# Versa64Cart_v1_4.net
KiCad netlist of a schematic drawn in EAGLE
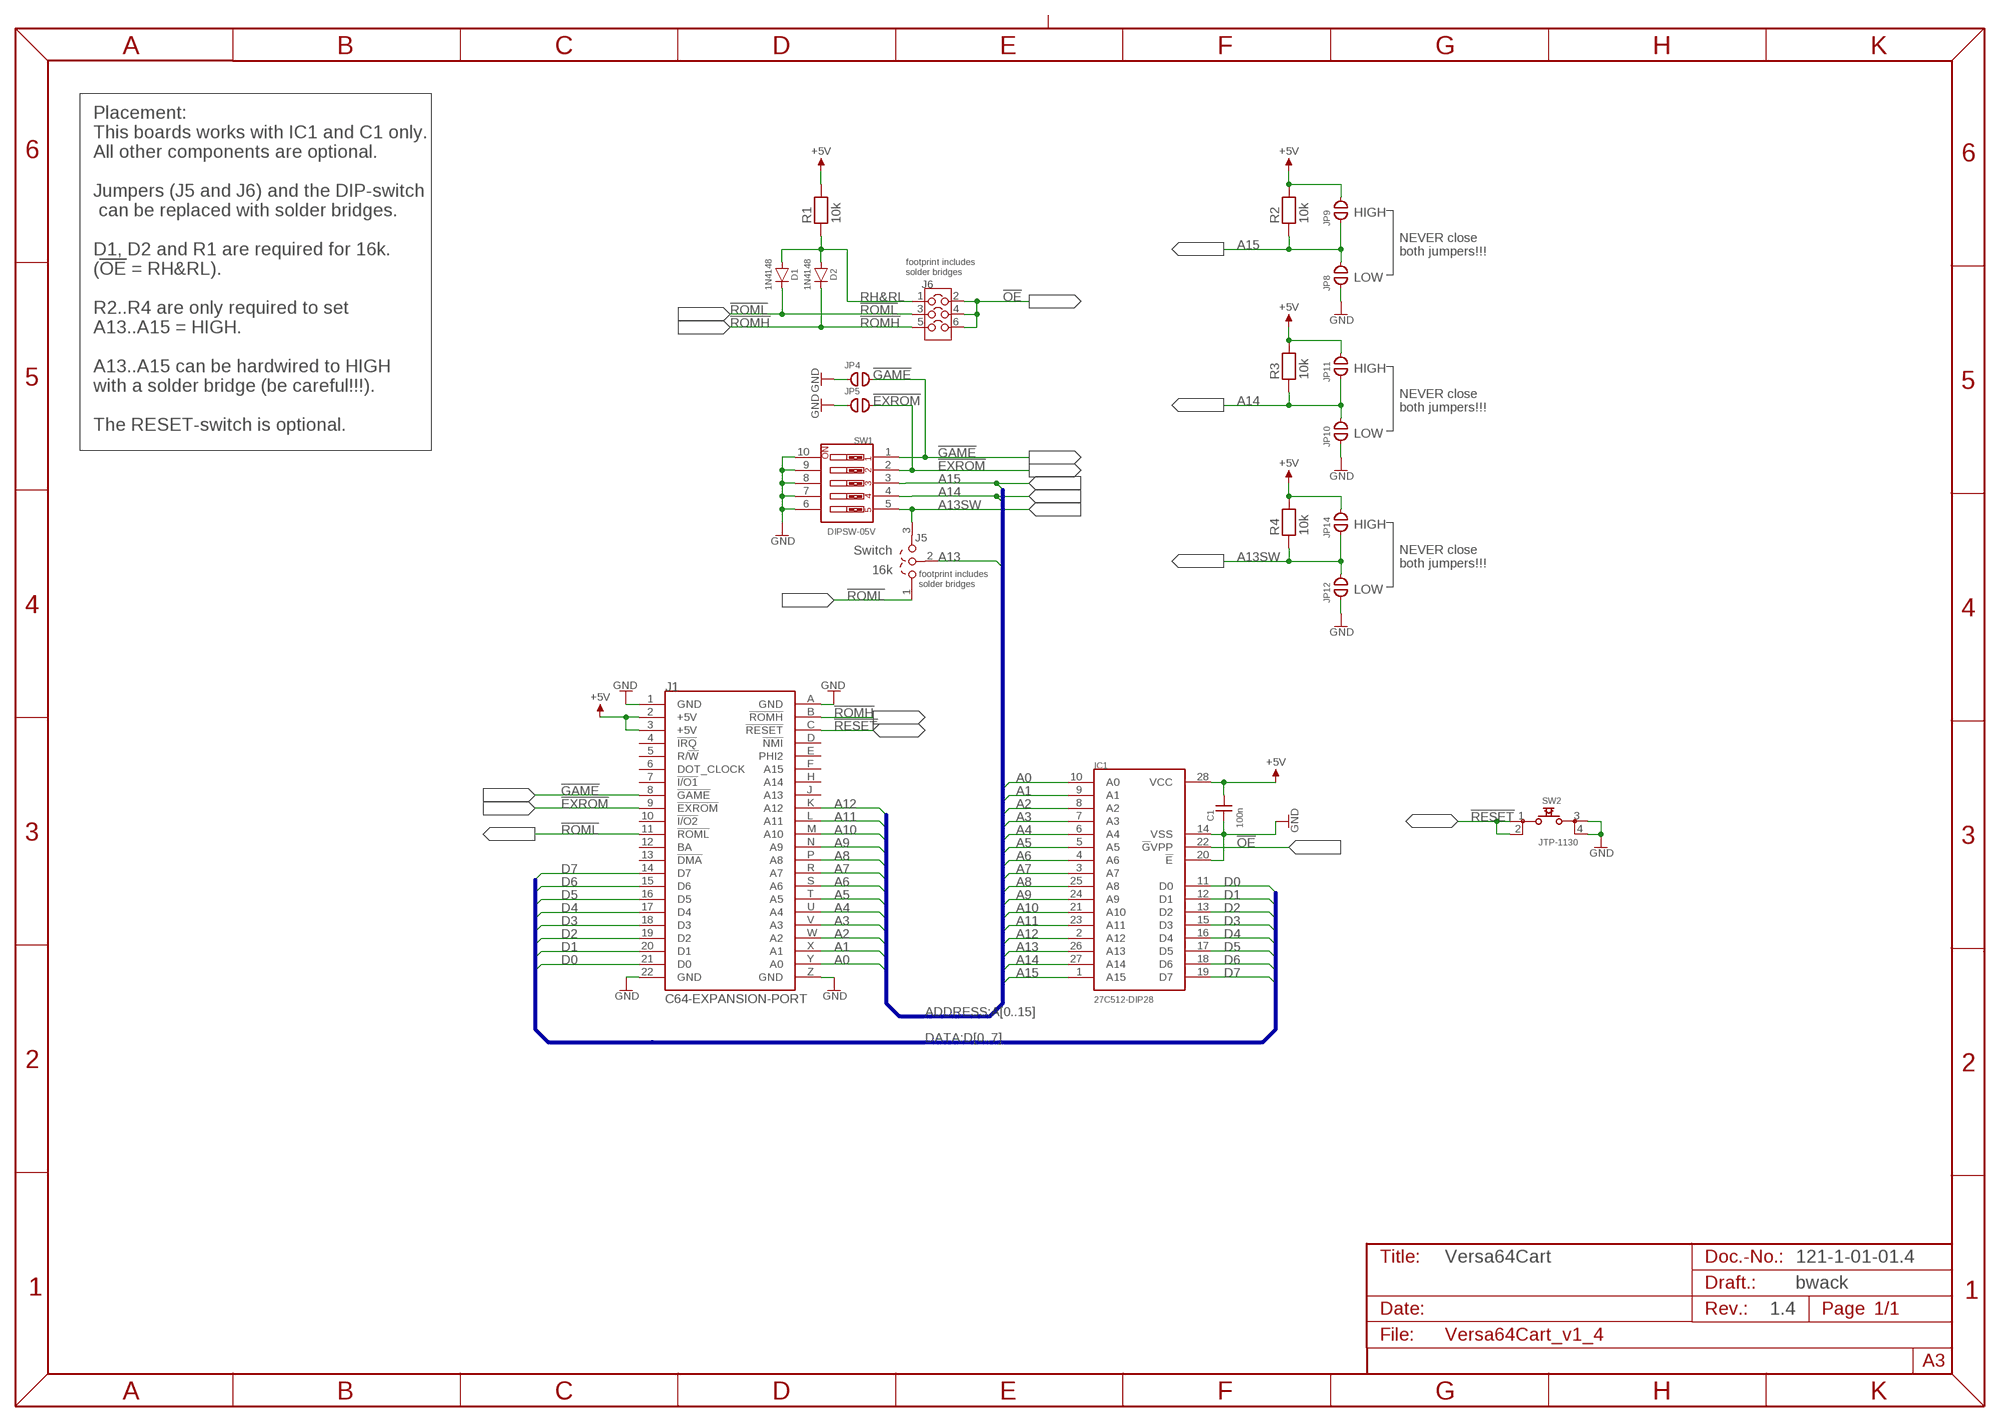
[diagram p0: schematic, sheet 1]

(export (version "E")
  (design (tool "Eeschema 10.0.6"))
  (components
    (comp (ref "C1")
      (value "100n")
      (footprint "eagle-import:C-2,5")
      (libsource (lib "eagle-import") (part "CAP01"))
    )
    (comp (ref "D1")
      (value "1N4148")
      (footprint "eagle-import:DO-35")
      (libsource (lib "eagle-import") (part "1N4148"))
    )
    (comp (ref "D2")
      (value "1N4148")
      (footprint "eagle-import:DO-35")
      (libsource (lib "eagle-import") (part "1N4148"))
    )
    (comp (ref "IC1")
      (value "27C512-DIP28")
      (footprint "eagle-import:DIL28-6")
      (libsource (lib "eagle-import") (part "M27C512-DIP28"))
    )
    (comp (ref "J1")
      (value "C64-EXPANSION-PORT")
      (footprint "eagle-import:EXPANSIO_SQ")
      (libsource (lib "eagle-import") (part "C64-EXPANSIONPNARROW"))
    )
    (comp (ref "J5")
      (value "COMBI-3P")
      (footprint "eagle-import:COMBI-3P")
      (libsource (lib "eagle-import") (part "COMBI-3P"))
    )
    (comp (ref "J6")
      (value "COMBI-3X2P")
      (footprint "eagle-import:COMBI-3X2")
      (fields (field (name "SPICEPREFIX") "X"))
      (libsource (lib "eagle-import") (part "COMBI-3X2P"))
    )
    (comp (ref "JP4")
      (value "OPEN")
      (footprint "eagle-import:CP_OP")
      (libsource (lib "eagle-import") (part "OPEN"))
    )
    (comp (ref "JP5")
      (value "OPEN")
      (footprint "eagle-import:CP_OP")
      (libsource (lib "eagle-import") (part "OPEN"))
    )
    (comp (ref "JP8")
      (value "OPEN")
      (footprint "eagle-import:CP_OP")
      (libsource (lib "eagle-import") (part "OPEN"))
    )
    (comp (ref "JP9")
      (value "OPEN")
      (footprint "eagle-import:CP_OP")
      (libsource (lib "eagle-import") (part "OPEN"))
    )
    (comp (ref "JP10")
      (value "OPEN")
      (footprint "eagle-import:CP_OP")
      (libsource (lib "eagle-import") (part "OPEN"))
    )
    (comp (ref "JP11")
      (value "OPEN")
      (footprint "eagle-import:CP_OP")
      (libsource (lib "eagle-import") (part "OPEN"))
    )
    (comp (ref "JP12")
      (value "OPEN")
      (footprint "eagle-import:CP_OP")
      (libsource (lib "eagle-import") (part "OPEN"))
    )
    (comp (ref "JP14")
      (value "OPEN")
      (footprint "eagle-import:CP_OP")
      (libsource (lib "eagle-import") (part "OPEN"))
    )
    (comp (ref "R1")
      (value "10k")
      (footprint "eagle-import:R-10")
      (libsource (lib "eagle-import") (part "RES04"))
    )
    (comp (ref "R2")
      (value "10k")
      (footprint "eagle-import:R-10")
      (libsource (lib "eagle-import") (part "RES04"))
    )
    (comp (ref "R3")
      (value "10k")
      (footprint "eagle-import:R-10")
      (libsource (lib "eagle-import") (part "RES04"))
    )
    (comp (ref "R4")
      (value "10k")
      (footprint "eagle-import:R-10")
      (libsource (lib "eagle-import") (part "RES04"))
    )
    (comp (ref "SW1")
      (value "DIPSW-05V")
      (footprint "eagle-import:DIPSW-05V")
      (libsource (lib "eagle-import") (part "DIPSW-05V"))
    )
    (comp (ref "SW2")
      (value "JTP-1130")
      (footprint "eagle-import:JTP-1130")
      (libsource (lib "eagle-import") (part "JTP-1130"))
    )
  )
  (nets
    (net (code "25") (name "+5V") (class "Default")
      (node (ref "C1") (pin "2") (pinfunction "2_2") (pintype "passive"))
      (node (ref "IC1") (pin "28") (pinfunction "VCC_28") (pintype "power_in"))
      (node (ref "J1") (pin "2") (pinfunction "+5V_2") (pintype "power_in"))
      (node (ref "J1") (pin "3") (pinfunction "+5V_3") (pintype "power_in"))
      (node (ref "JP11") (pin "2") (pinfunction "2_2") (pintype "passive"))
      (node (ref "JP14") (pin "2") (pinfunction "2_2") (pintype "passive"))
      (node (ref "JP9") (pin "2") (pinfunction "2_2") (pintype "passive"))
      (node (ref "R1") (pin "2") (pinfunction "2_2") (pintype "passive"))
      (node (ref "R2") (pin "2") (pinfunction "2_2") (pintype "passive"))
      (node (ref "R3") (pin "2") (pinfunction "2_2") (pintype "passive"))
      (node (ref "R4") (pin "2") (pinfunction "2_2") (pintype "passive"))
    )
    (net (code "26") (name "/A0") (class "Default")
      (node (ref "IC1") (pin "10") (pinfunction "A0_10") (pintype "input"))
      (node (ref "J1") (pin "Y") (pinfunction "A0_Y") (pintype "bidirectional"))
    )
    (net (code "27") (name "/A1") (class "Default")
      (node (ref "IC1") (pin "9") (pinfunction "A1_9") (pintype "input"))
      (node (ref "J1") (pin "X") (pinfunction "A1_X") (pintype "bidirectional"))
    )
    (net (code "28") (name "/A2") (class "Default")
      (node (ref "IC1") (pin "8") (pinfunction "A2_8") (pintype "input"))
      (node (ref "J1") (pin "W") (pinfunction "A2_W") (pintype "bidirectional"))
    )
    (net (code "29") (name "/A3") (class "Default")
      (node (ref "IC1") (pin "7") (pinfunction "A3_7") (pintype "input"))
      (node (ref "J1") (pin "V") (pinfunction "A3_V") (pintype "bidirectional"))
    )
    (net (code "30") (name "/A4") (class "Default")
      (node (ref "IC1") (pin "6") (pinfunction "A4_6") (pintype "input"))
      (node (ref "J1") (pin "U") (pinfunction "A4_U") (pintype "bidirectional"))
    )
    (net (code "31") (name "/A5") (class "Default")
      (node (ref "IC1") (pin "5") (pinfunction "A5_5") (pintype "input"))
      (node (ref "J1") (pin "T") (pinfunction "A5_T") (pintype "bidirectional"))
    )
    (net (code "32") (name "/A6") (class "Default")
      (node (ref "IC1") (pin "4") (pinfunction "A6_4") (pintype "input"))
      (node (ref "J1") (pin "S") (pinfunction "A6_S") (pintype "bidirectional"))
    )
    (net (code "33") (name "/A7") (class "Default")
      (node (ref "IC1") (pin "3") (pinfunction "A7_3") (pintype "input"))
      (node (ref "J1") (pin "R") (pinfunction "A7_R") (pintype "bidirectional"))
    )
    (net (code "34") (name "/A8") (class "Default")
      (node (ref "IC1") (pin "25") (pinfunction "A8_25") (pintype "input"))
      (node (ref "J1") (pin "P") (pinfunction "A8_P") (pintype "bidirectional"))
    )
    (net (code "35") (name "/A9") (class "Default")
      (node (ref "IC1") (pin "24") (pinfunction "A9_24") (pintype "input"))
      (node (ref "J1") (pin "N") (pinfunction "A9_N") (pintype "bidirectional"))
    )
    (net (code "36") (name "/A10") (class "Default")
      (node (ref "IC1") (pin "21") (pinfunction "A10_21") (pintype "input"))
      (node (ref "J1") (pin "M") (pinfunction "A10_M") (pintype "bidirectional"))
    )
    (net (code "37") (name "/A11") (class "Default")
      (node (ref "IC1") (pin "23") (pinfunction "A11_23") (pintype "input"))
      (node (ref "J1") (pin "L") (pinfunction "A11_L") (pintype "bidirectional"))
    )
    (net (code "38") (name "/A12") (class "Default")
      (node (ref "IC1") (pin "2") (pinfunction "A12_2") (pintype "input"))
      (node (ref "J1") (pin "K") (pinfunction "A12_K") (pintype "bidirectional"))
    )
    (net (code "39") (name "/A13") (class "Default")
      (node (ref "IC1") (pin "26") (pinfunction "A13_26") (pintype "input"))
      (node (ref "J5") (pin "2") (pinfunction "2_2") (pintype "bidirectional"))
    )
    (net (code "40") (name "/A13SW") (class "Default")
      (node (ref "J5") (pin "3") (pinfunction "3_3") (pintype "bidirectional"))
      (node (ref "JP12") (pin "2") (pinfunction "2_2") (pintype "passive"))
      (node (ref "JP14") (pin "1") (pinfunction "1_1") (pintype "passive"))
      (node (ref "R4") (pin "1") (pinfunction "1_1") (pintype "passive"))
      (node (ref "SW1") (pin "5") (pinfunction "5_5") (pintype "passive"))
    )
    (net (code "41") (name "/A14") (class "Default")
      (node (ref "IC1") (pin "27") (pinfunction "A14_27") (pintype "input"))
      (node (ref "JP10") (pin "2") (pinfunction "2_2") (pintype "passive"))
      (node (ref "JP11") (pin "1") (pinfunction "1_1") (pintype "passive"))
      (node (ref "R3") (pin "1") (pinfunction "1_1") (pintype "passive"))
      (node (ref "SW1") (pin "4") (pinfunction "4_4") (pintype "passive"))
    )
    (net (code "42") (name "/A15") (class "Default")
      (node (ref "IC1") (pin "1") (pinfunction "A15_1") (pintype "input"))
      (node (ref "JP8") (pin "2") (pinfunction "2_2") (pintype "passive"))
      (node (ref "JP9") (pin "1") (pinfunction "1_1") (pintype "passive"))
      (node (ref "R2") (pin "1") (pinfunction "1_1") (pintype "passive"))
      (node (ref "SW1") (pin "3") (pinfunction "3_3") (pintype "passive"))
    )
    (net (code "44") (name "/D0") (class "Default")
      (node (ref "IC1") (pin "11") (pinfunction "D0_11") (pintype "bidirectional"))
      (node (ref "J1") (pin "21") (pinfunction "D0_21") (pintype "bidirectional"))
    )
    (net (code "45") (name "/D1") (class "Default")
      (node (ref "IC1") (pin "12") (pinfunction "D1_12") (pintype "bidirectional"))
      (node (ref "J1") (pin "20") (pinfunction "D1_20") (pintype "bidirectional"))
    )
    (net (code "46") (name "/D2") (class "Default")
      (node (ref "IC1") (pin "13") (pinfunction "D2_13") (pintype "bidirectional"))
      (node (ref "J1") (pin "19") (pinfunction "D2_19") (pintype "bidirectional"))
    )
    (net (code "47") (name "/D3") (class "Default")
      (node (ref "IC1") (pin "15") (pinfunction "D3_15") (pintype "bidirectional"))
      (node (ref "J1") (pin "18") (pinfunction "D3_18") (pintype "bidirectional"))
    )
    (net (code "48") (name "/D4") (class "Default")
      (node (ref "IC1") (pin "16") (pinfunction "D4_16") (pintype "bidirectional"))
      (node (ref "J1") (pin "17") (pinfunction "D4_17") (pintype "bidirectional"))
    )
    (net (code "49") (name "/D5") (class "Default")
      (node (ref "IC1") (pin "17") (pinfunction "D5_17") (pintype "bidirectional"))
      (node (ref "J1") (pin "16") (pinfunction "D5_16") (pintype "bidirectional"))
    )
    (net (code "50") (name "/D6") (class "Default")
      (node (ref "IC1") (pin "18") (pinfunction "D6_18") (pintype "bidirectional"))
      (node (ref "J1") (pin "15") (pinfunction "D6_15") (pintype "bidirectional"))
    )
    (net (code "51") (name "/D7") (class "Default")
      (node (ref "IC1") (pin "19") (pinfunction "D7_19") (pintype "bidirectional"))
      (node (ref "J1") (pin "14") (pinfunction "D7_14") (pintype "bidirectional"))
    )
    (net (code "53") (name "/RH&RL") (class "Default")
      (node (ref "D1") (pin "A") (pinfunction "A_A") (pintype "passive"))
      (node (ref "D2") (pin "A") (pinfunction "A_A") (pintype "passive"))
      (node (ref "J6") (pin "1") (pinfunction "1_1") (pintype "bidirectional"))
      (node (ref "R1") (pin "1") (pinfunction "1_1") (pintype "passive"))
    )
    (net (code "54") (name "/~{EXROM}") (class "Default")
      (node (ref "J1") (pin "9") (pinfunction "~{EXROM}_9") (pintype "input"))
      (node (ref "JP5") (pin "2") (pinfunction "2_2") (pintype "passive"))
      (node (ref "SW1") (pin "2") (pinfunction "2_2") (pintype "passive"))
    )
    (net (code "55") (name "/~{GAME}") (class "Default")
      (node (ref "J1") (pin "8") (pinfunction "~{GAME}_8") (pintype "input"))
      (node (ref "JP4") (pin "2") (pinfunction "2_2") (pintype "passive"))
      (node (ref "SW1") (pin "1") (pinfunction "1_1") (pintype "passive"))
    )
    (net (code "56") (name "/~{OE}") (class "Default")
      (node (ref "IC1") (pin "22") (pinfunction "~{G}VPP_22") (pintype "input"))
      (node (ref "J6") (pin "2") (pinfunction "2_2") (pintype "bidirectional"))
      (node (ref "J6") (pin "4") (pinfunction "4_4") (pintype "bidirectional"))
      (node (ref "J6") (pin "6") (pinfunction "6_6") (pintype "bidirectional"))
    )
    (net (code "57") (name "/~{RESET}") (class "Default")
      (node (ref "J1") (pin "C") (pinfunction "~{RESET}_C") (pintype "open_collector"))
      (node (ref "SW2") (pin "1") (pinfunction "1_1") (pintype "passive"))
      (node (ref "SW2") (pin "2") (pinfunction "2_2") (pintype "passive"))
    )
    (net (code "58") (name "/~{ROMH}") (class "Default")
      (node (ref "D2") (pin "K") (pinfunction "K_K") (pintype "passive"))
      (node (ref "J1") (pin "B") (pinfunction "~{ROMH}_B") (pintype "output"))
      (node (ref "J6") (pin "5") (pinfunction "5_5") (pintype "bidirectional"))
    )
    (net (code "59") (name "/~{ROML}") (class "Default")
      (node (ref "D1") (pin "K") (pinfunction "K_K") (pintype "passive"))
      (node (ref "J1") (pin "11") (pinfunction "~{ROML}_11") (pintype "output"))
      (node (ref "J5") (pin "1") (pinfunction "1_1") (pintype "bidirectional"))
      (node (ref "J6") (pin "3") (pinfunction "3_3") (pintype "bidirectional"))
    )
    (net (code "60") (name "GND") (class "Default")
      (node (ref "C1") (pin "1") (pinfunction "1_1") (pintype "passive"))
      (node (ref "IC1") (pin "14") (pinfunction "VSS_14") (pintype "power_in"))
      (node (ref "IC1") (pin "20") (pinfunction "~{E}_20") (pintype "input"))
      (node (ref "J1") (pin "1") (pinfunction "GND_1") (pintype "power_in"))
      (node (ref "J1") (pin "22") (pinfunction "GND_22") (pintype "power_in"))
      (node (ref "J1") (pin "A") (pinfunction "GND_A") (pintype "power_in"))
      (node (ref "J1") (pin "Z") (pinfunction "GND_Z") (pintype "power_in"))
      (node (ref "JP10") (pin "1") (pinfunction "1_1") (pintype "passive"))
      (node (ref "JP12") (pin "1") (pinfunction "1_1") (pintype "passive"))
      (node (ref "JP4") (pin "1") (pinfunction "1_1") (pintype "passive"))
      (node (ref "JP5") (pin "1") (pinfunction "1_1") (pintype "passive"))
      (node (ref "JP8") (pin "1") (pinfunction "1_1") (pintype "passive"))
      (node (ref "SW1") (pin "10") (pinfunction "10_10") (pintype "passive"))
      (node (ref "SW1") (pin "6") (pinfunction "6_6") (pintype "passive"))
      (node (ref "SW1") (pin "7") (pinfunction "7_7") (pintype "passive"))
      (node (ref "SW1") (pin "8") (pinfunction "8_8") (pintype "passive"))
      (node (ref "SW1") (pin "9") (pinfunction "9_9") (pintype "passive"))
      (node (ref "SW2") (pin "3") (pinfunction "3_3") (pintype "passive"))
      (node (ref "SW2") (pin "4") (pinfunction "4_4") (pintype "passive"))
    )
    (net (code "61") (name "unconnected-(J1-A13-PadJ)") (class "Default")
      (node (ref "J1") (pin "J") (pinfunction "A13_J") (pintype "bidirectional"))
    )
    (net (code "62") (name "unconnected-(J1-A14-PadH)") (class "Default")
      (node (ref "J1") (pin "H") (pinfunction "A14_H") (pintype "bidirectional"))
    )
    (net (code "63") (name "unconnected-(J1-A15-PadF)") (class "Default")
      (node (ref "J1") (pin "F") (pinfunction "A15_F") (pintype "bidirectional"))
    )
    (net (code "64") (name "unconnected-(J1-BA-Pad12)") (class "Default")
      (node (ref "J1") (pin "12") (pinfunction "BA_12") (pintype "output"))
    )
    (net (code "65") (name "unconnected-(J1-DOT_CLOCK-Pad6)") (class "Default")
      (node (ref "J1") (pin "6") (pinfunction "DOT_CLOCK_6") (pintype "output"))
    )
    (net (code "66") (name "unconnected-(J1-PHI2-PadE)") (class "Default")
      (node (ref "J1") (pin "E") (pinfunction "PHI2_E") (pintype "output"))
    )
    (net (code "67") (name "unconnected-(J1-R{slash}~{W}-Pad5)") (class "Default")
      (node (ref "J1") (pin "5") (pinfunction "R/~{W}_5") (pintype "output"))
    )
    (net (code "68") (name "unconnected-(J1-~{DMA}-Pad13)") (class "Default")
      (node (ref "J1") (pin "13") (pinfunction "~{DMA}_13") (pintype "input"))
    )
    (net (code "69") (name "unconnected-(J1-~{IRQ}-Pad4)") (class "Default")
      (node (ref "J1") (pin "4") (pinfunction "~{IRQ}_4") (pintype "input"))
    )
    (net (code "70") (name "unconnected-(J1-~{I{slash}O1}-Pad7)") (class "Default")
      (node (ref "J1") (pin "7") (pinfunction "~{I/O1}_7") (pintype "output"))
    )
    (net (code "71") (name "unconnected-(J1-~{I{slash}O2}-Pad10)") (class "Default")
      (node (ref "J1") (pin "10") (pinfunction "~{I/O2}_10") (pintype "output"))
    )
    (net (code "72") (name "unconnected-(J1-~{NMI}-PadD)") (class "Default")
      (node (ref "J1") (pin "D") (pinfunction "~{NMI}_D") (pintype "input"))
    )
  )
)
